# Controller_Board_DS-PI.net
KiCad netlist of a schematic drawn in EasyEDA Pro
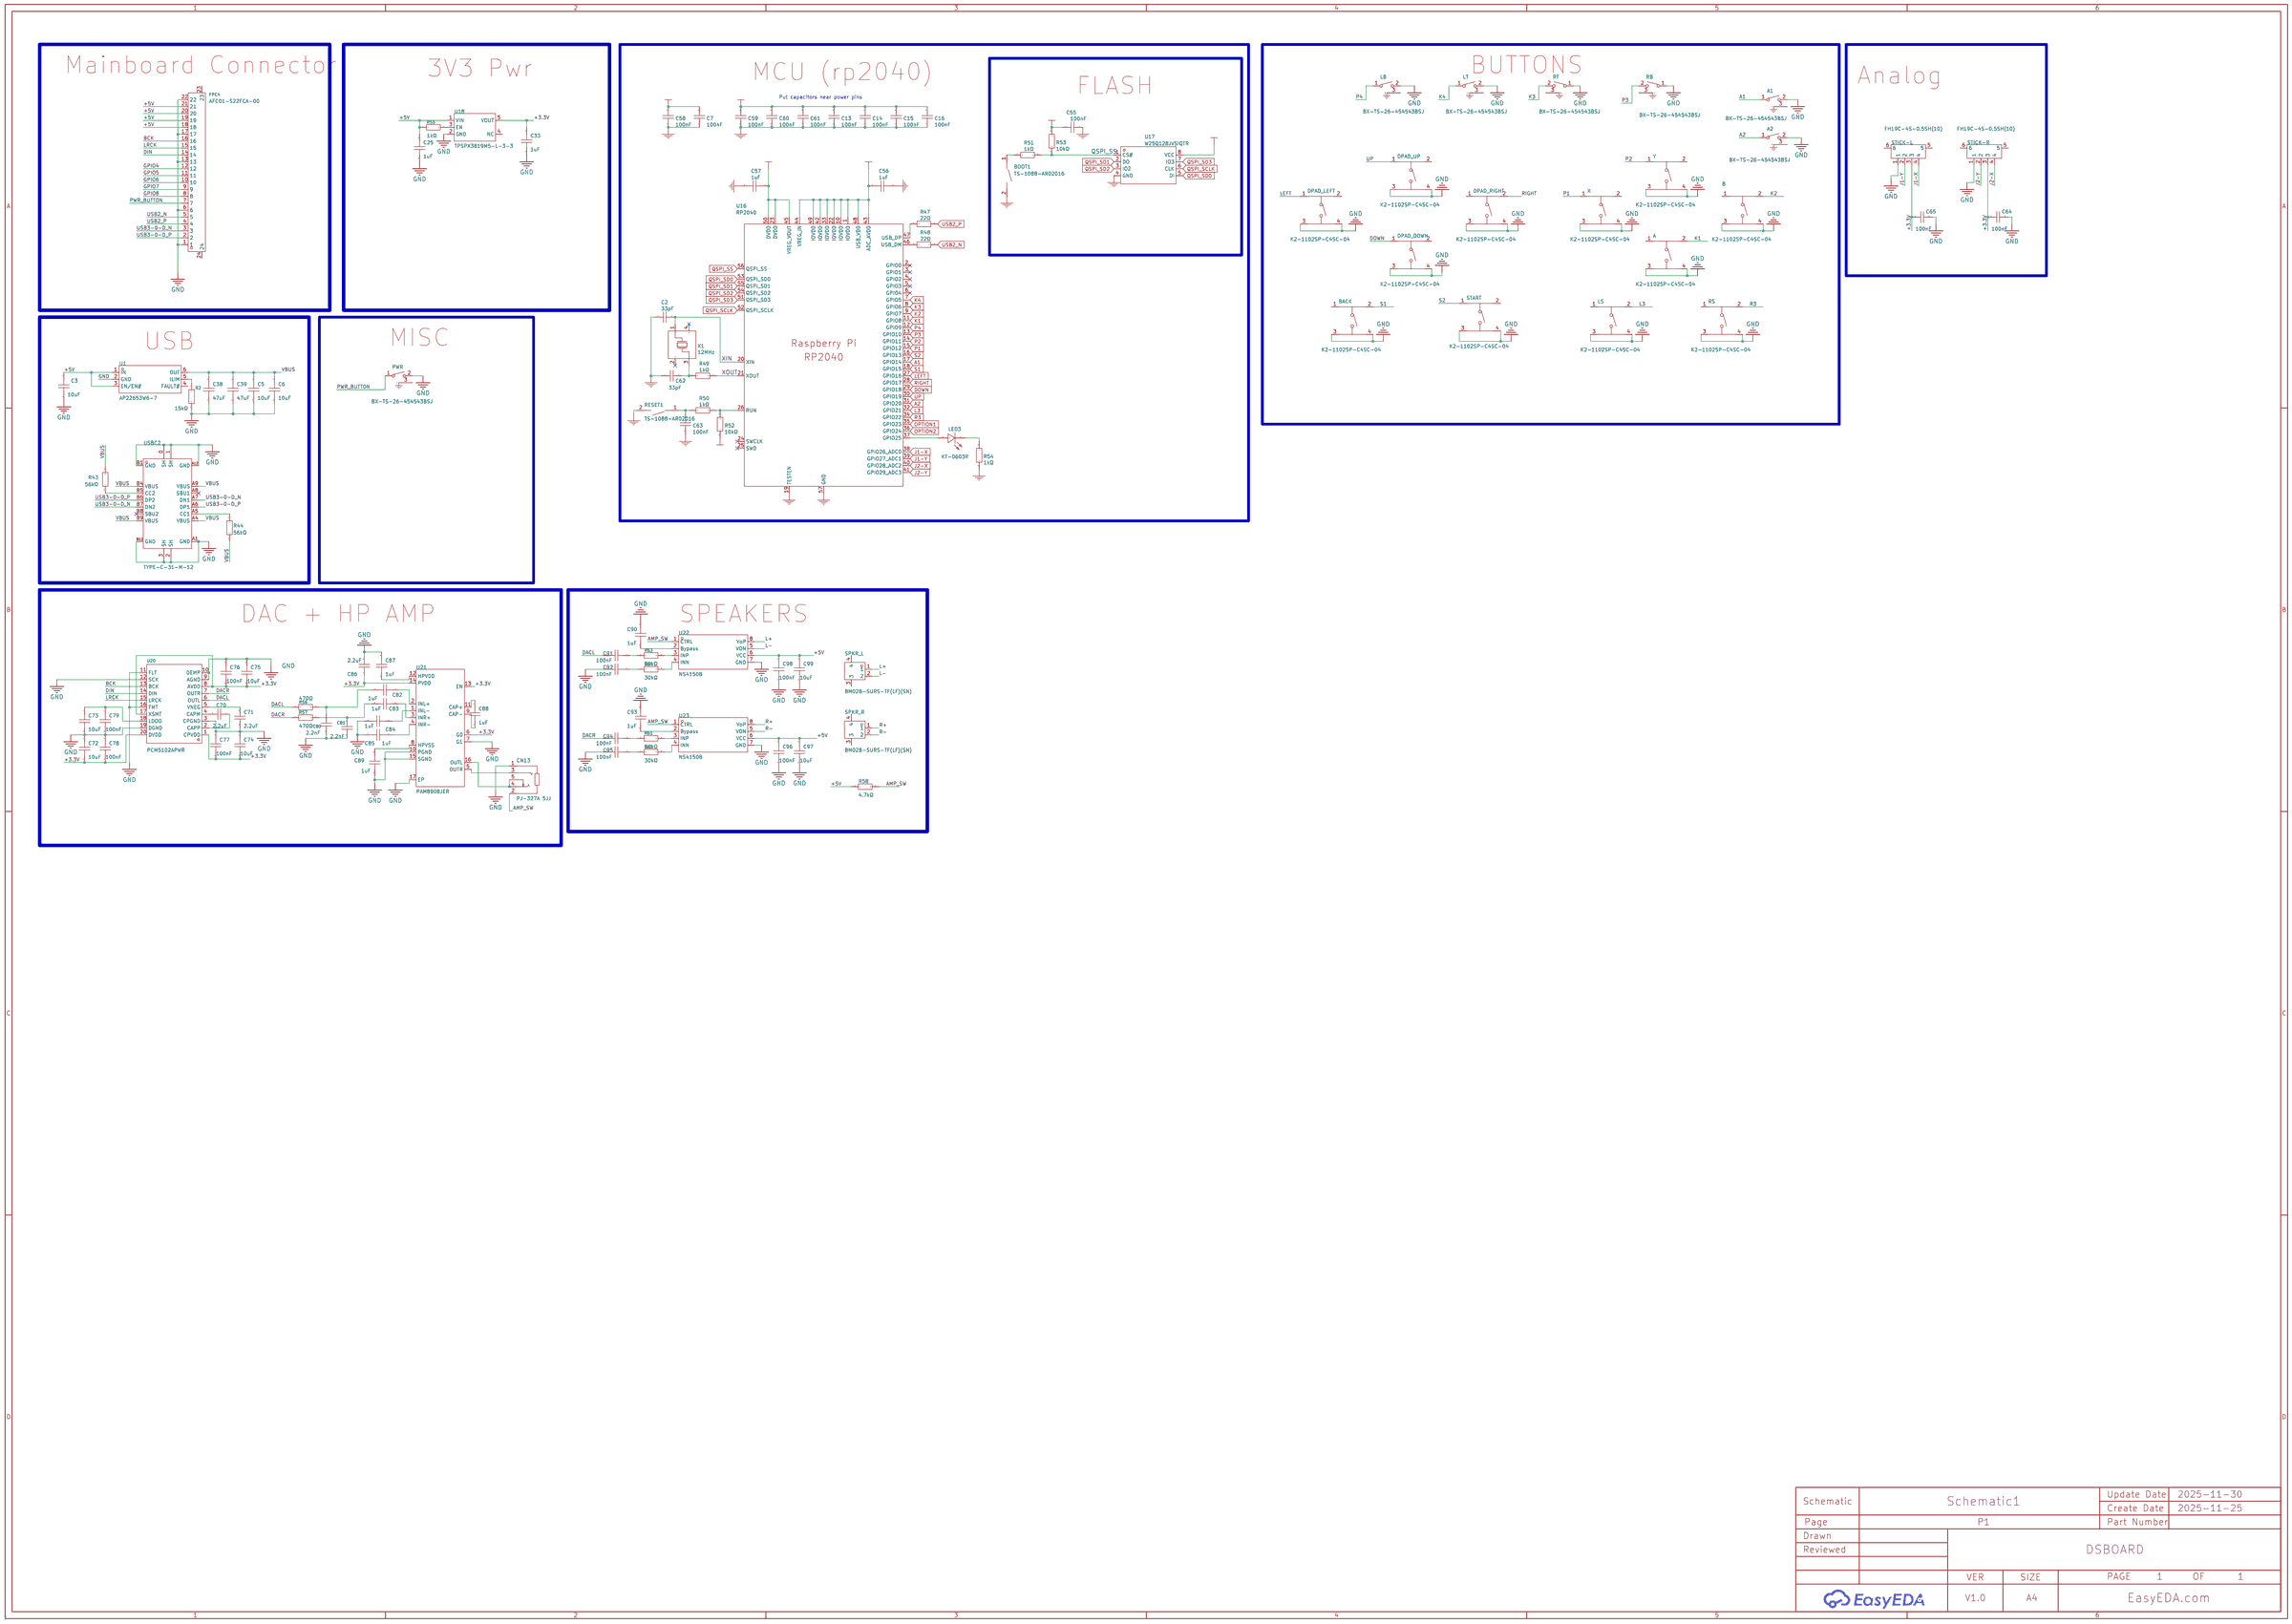
[diagram p0: schematic sheet]

(export (version "E")
  (design (tool "Eeschema 10.0.6"))
  (components
    (comp (ref "A")
      (value "K2-1102SP-C4SC-04")
      (footprint "easyedapro:KEY-SMD_4P-L6.0-W6.0-P4.50-LS9.5-BL")
      (fields (field (name "Manufacturer") "韩国韩荣"))
      (libsource (lib "easyedapro") (part "K2-1102SP-C4SC-04"))
    )
    (comp (ref "A1")
      (value "BX-TS-26-454543BSJ")
      (footprint "easyedapro:SW-TH_3P-L4.5-W4.3-P3.00-LS1.9")
      (fields (field (name "Manufacturer") "Bossie(博锡)"))
      (libsource (lib "easyedapro") (part "BX-TS-26-454543BSJ"))
    )
    (comp (ref "A2")
      (value "BX-TS-26-454543BSJ")
      (footprint "easyedapro:SW-TH_3P-L4.5-W4.3-P3.00-LS1.9")
      (fields (field (name "Manufacturer") "Bossie(博锡)"))
      (libsource (lib "easyedapro") (part "BX-TS-26-454543BSJ"))
    )
    (comp (ref "B")
      (value "K2-1102SP-C4SC-04")
      (footprint "easyedapro:KEY-SMD_4P-L6.0-W6.0-P4.50-LS9.5-BL")
      (fields (field (name "Manufacturer") "韩国韩荣"))
      (libsource (lib "easyedapro") (part "K2-1102SP-C4SC-04"))
    )
    (comp (ref "BACK")
      (value "K2-1102SP-C4SC-04")
      (footprint "easyedapro:KEY-SMD_4P-L6.0-W6.0-P4.50-LS9.5-BL")
      (fields (field (name "Manufacturer") "韩国韩荣"))
      (libsource (lib "easyedapro") (part "K2-1102SP-C4SC-04"))
    )
    (comp (ref "BOOT1")
      (value "TS-1088-AR02016")
      (footprint "easyedapro:SW-SMD_L3.9-W3.0-P4.45")
      (fields (field (name "Manufacturer") "XUNPU(讯普)"))
      (libsource (lib "easyedapro") (part "TS-1088-AR02016"))
    )
    (comp (ref "C2")
      (value "33pF")
      (footprint "easyedapro:C0402")
      (fields (field (name "Manufacturer Part") "0402CG330J500NT") (field (name "Manufacturer") "FH(风华)"))
      (libsource (lib "easyedapro") (part "33pF"))
    )
    (comp (ref "C3")
      (value "10uF")
      (footprint "easyedapro:C0805")
      (fields
        (field (name "Manufacturer Part") "CL21A106KAYNNNE")
        (field (name "Manufacturer") "SAMSUNG(三星)")
      )
      (libsource (lib "easyedapro") (part "CL21A106KAYNNNE"))
    )
    (comp (ref "C5")
      (value "10uF")
      (footprint "easyedapro:C0805")
      (fields
        (field (name "Manufacturer Part") "CL21A106KAYNNNE")
        (field (name "Manufacturer") "SAMSUNG(三星)")
      )
      (libsource (lib "easyedapro") (part "CL21A106KAYNNNE"))
    )
    (comp (ref "C6")
      (value "10uF")
      (footprint "easyedapro:C0805")
      (fields
        (field (name "Manufacturer Part") "CL21A106KAYNNNE")
        (field (name "Manufacturer") "SAMSUNG(三星)")
      )
      (libsource (lib "easyedapro") (part "CL21A106KAYNNNE"))
    )
    (comp (ref "C7")
      (value "100nF")
      (footprint "easyedapro:C0402_NEW")
      (fields
        (field (name "Manufacturer Part") "CL05B104KO5NNNC")
        (field (name "Manufacturer") "SAMSUNG(三星)")
      )
      (libsource (lib "easyedapro") (part "100nF"))
    )
    (comp (ref "C13")
      (value "100nF")
      (footprint "easyedapro:C0402_NEW")
      (fields
        (field (name "Manufacturer Part") "CL05B104KO5NNNC")
        (field (name "Manufacturer") "SAMSUNG(三星)")
      )
      (libsource (lib "easyedapro") (part "100nF"))
    )
    (comp (ref "C14")
      (value "100nF")
      (footprint "easyedapro:C0402_NEW")
      (fields
        (field (name "Manufacturer Part") "CL05B104KO5NNNC")
        (field (name "Manufacturer") "SAMSUNG(三星)")
      )
      (libsource (lib "easyedapro") (part "100nF"))
    )
    (comp (ref "C15")
      (value "100nF")
      (footprint "easyedapro:C0402_NEW")
      (fields
        (field (name "Manufacturer Part") "CL05B104KO5NNNC")
        (field (name "Manufacturer") "SAMSUNG(三星)")
      )
      (libsource (lib "easyedapro") (part "100nF"))
    )
    (comp (ref "C16")
      (value "100nF")
      (footprint "easyedapro:C0402_NEW")
      (fields
        (field (name "Manufacturer Part") "CL05B104KO5NNNC")
        (field (name "Manufacturer") "SAMSUNG(三星)")
      )
      (libsource (lib "easyedapro") (part "100nF"))
    )
    (comp (ref "C25")
      (value "1uF")
      (footprint "easyedapro:C0603")
      (fields
        (field (name "Manufacturer Part") "CL10A105KB8NNNC")
        (field (name "Manufacturer") "SAMSUNG(三星)")
      )
      (libsource (lib "easyedapro") (part "CL10A105KB8NNNC"))
    )
    (comp (ref "C33")
      (value "1uF")
      (footprint "easyedapro:C0603")
      (fields
        (field (name "Manufacturer Part") "CL10A105KB8NNNC")
        (field (name "Manufacturer") "SAMSUNG(三星)")
      )
      (libsource (lib "easyedapro") (part "CL10A105KB8NNNC"))
    )
    (comp (ref "C38")
      (value "47uF")
      (footprint "easyedapro:C1206")
      (fields
        (field (name "Manufacturer Part") "CL31A476MPHNNNE")
        (field (name "Manufacturer") "SAMSUNG(三星)")
      )
      (libsource (lib "easyedapro") (part "CL31A476MPHNNNE"))
    )
    (comp (ref "C39")
      (value "47uF")
      (footprint "easyedapro:C1206")
      (fields
        (field (name "Manufacturer Part") "CL31A476MPHNNNE")
        (field (name "Manufacturer") "SAMSUNG(三星)")
      )
      (libsource (lib "easyedapro") (part "CL31A476MPHNNNE"))
    )
    (comp (ref "C55")
      (value "100nF")
      (footprint "easyedapro:C0402_NEW")
      (fields
        (field (name "Manufacturer Part") "CL05B104KO5NNNC")
        (field (name "Manufacturer") "SAMSUNG(三星)")
      )
      (libsource (lib "easyedapro") (part "100nF"))
    )
    (comp (ref "C56")
      (value "1uF")
      (footprint "easyedapro:C0402")
      (fields
        (field (name "Manufacturer Part") "CL05A105KA5NQNC")
        (field (name "Manufacturer") "SAMSUNG(三星)")
      )
      (libsource (lib "easyedapro") (part "1uF"))
    )
    (comp (ref "C57")
      (value "1uF")
      (footprint "easyedapro:C0402")
      (fields
        (field (name "Manufacturer Part") "CL05A105KA5NQNC")
        (field (name "Manufacturer") "SAMSUNG(三星)")
      )
      (libsource (lib "easyedapro") (part "1uF"))
    )
    (comp (ref "C58")
      (value "100nF")
      (footprint "easyedapro:C0402_NEW")
      (fields
        (field (name "Manufacturer Part") "CL05B104KO5NNNC")
        (field (name "Manufacturer") "SAMSUNG(三星)")
      )
      (libsource (lib "easyedapro") (part "100nF"))
    )
    (comp (ref "C59")
      (value "100nF")
      (footprint "easyedapro:C0402_NEW")
      (fields
        (field (name "Manufacturer Part") "CL05B104KO5NNNC")
        (field (name "Manufacturer") "SAMSUNG(三星)")
      )
      (libsource (lib "easyedapro") (part "100nF"))
    )
    (comp (ref "C60")
      (value "100nF")
      (footprint "easyedapro:C0402_NEW")
      (fields
        (field (name "Manufacturer Part") "CL05B104KO5NNNC")
        (field (name "Manufacturer") "SAMSUNG(三星)")
      )
      (libsource (lib "easyedapro") (part "100nF"))
    )
    (comp (ref "C61")
      (value "100nF")
      (footprint "easyedapro:C0402_NEW")
      (fields
        (field (name "Manufacturer Part") "CL05B104KO5NNNC")
        (field (name "Manufacturer") "SAMSUNG(三星)")
      )
      (libsource (lib "easyedapro") (part "100nF"))
    )
    (comp (ref "C62")
      (value "33pF")
      (footprint "easyedapro:C0402")
      (fields (field (name "Manufacturer Part") "0402CG330J500NT") (field (name "Manufacturer") "FH(风华)"))
      (libsource (lib "easyedapro") (part "33pF"))
    )
    (comp (ref "C63")
      (value "100nF")
      (footprint "easyedapro:C0402_NEW")
      (fields
        (field (name "Manufacturer Part") "CL05B104KO5NNNC")
        (field (name "Manufacturer") "SAMSUNG(三星)")
      )
      (libsource (lib "easyedapro") (part "100nF"))
    )
    (comp (ref "C64")
      (value "100nF")
      (footprint "easyedapro:C0402_NEW")
      (fields
        (field (name "Manufacturer Part") "CL05B104KO5NNNC")
        (field (name "Manufacturer") "SAMSUNG(三星)")
      )
      (libsource (lib "easyedapro") (part "100nF"))
    )
    (comp (ref "C65")
      (value "100nF")
      (footprint "easyedapro:C0402_NEW")
      (fields
        (field (name "Manufacturer Part") "CL05B104KO5NNNC")
        (field (name "Manufacturer") "SAMSUNG(三星)")
      )
      (libsource (lib "easyedapro") (part "100nF"))
    )
    (comp (ref "C70")
      (value "2.2uF")
      (footprint "easyedapro:C0603")
      (fields
        (field (name "Manufacturer Part") "CL10A225KO8NNNC")
        (field (name "Manufacturer") "SAMSUNG(三星)")
      )
      (libsource (lib "easyedapro") (part "CL10A225KO8NNNC"))
    )
    (comp (ref "C71")
      (value "2.2uF")
      (footprint "easyedapro:C0603")
      (fields
        (field (name "Manufacturer Part") "CL10A225KO8NNNC")
        (field (name "Manufacturer") "SAMSUNG(三星)")
      )
      (libsource (lib "easyedapro") (part "CL10A225KO8NNNC"))
    )
    (comp (ref "C72")
      (value "10uF")
      (footprint "easyedapro:C0805")
      (fields
        (field (name "Manufacturer Part") "GRM21BR61H106KE43L")
        (field (name "Manufacturer") "muRata(村田)")
      )
      (libsource (lib "easyedapro") (part "GRM21BR61H106KE43L"))
    )
    (comp (ref "C73")
      (value "10uF")
      (footprint "easyedapro:C0805")
      (fields
        (field (name "Manufacturer Part") "GRM21BR61H106KE43L")
        (field (name "Manufacturer") "muRata(村田)")
      )
      (libsource (lib "easyedapro") (part "GRM21BR61H106KE43L"))
    )
    (comp (ref "C74")
      (value "10uF")
      (footprint "easyedapro:C0805")
      (fields
        (field (name "Manufacturer Part") "GRM21BR61H106KE43L")
        (field (name "Manufacturer") "muRata(村田)")
      )
      (libsource (lib "easyedapro") (part "GRM21BR61H106KE43L"))
    )
    (comp (ref "C75")
      (value "10uF")
      (footprint "easyedapro:C0805")
      (fields
        (field (name "Manufacturer Part") "GRM21BR61H106KE43L")
        (field (name "Manufacturer") "muRata(村田)")
      )
      (libsource (lib "easyedapro") (part "GRM21BR61H106KE43L"))
    )
    (comp (ref "C76")
      (value "100nF")
      (footprint "easyedapro:C0603")
      (description "Capacitance:100nF Tolerance:±10% Tolerance:±10% Voltage Rating:50V Temperature Coefficient:X7R")
      (fields
        (field (name "Manufacturer Part") "CC0603KRX7R9BB104")
        (field (name "Manufacturer") "YAGEO(国巨)")
      )
      (libsource (lib "easyedapro") (part "CC0603KRX7R9BB104"))
    )
    (comp (ref "C77")
      (value "100nF")
      (footprint "easyedapro:C0603")
      (description "Capacitance:100nF Tolerance:±10% Tolerance:±10% Voltage Rating:50V Temperature Coefficient:X7R")
      (fields
        (field (name "Manufacturer Part") "CC0603KRX7R9BB104")
        (field (name "Manufacturer") "YAGEO(国巨)")
      )
      (libsource (lib "easyedapro") (part "CC0603KRX7R9BB104"))
    )
    (comp (ref "C78")
      (value "100nF")
      (footprint "easyedapro:C0603")
      (description "Capacitance:100nF Tolerance:±10% Tolerance:±10% Voltage Rating:50V Temperature Coefficient:X7R")
      (fields
        (field (name "Manufacturer Part") "CC0603KRX7R9BB104")
        (field (name "Manufacturer") "YAGEO(国巨)")
      )
      (libsource (lib "easyedapro") (part "CC0603KRX7R9BB104"))
    )
    (comp (ref "C79")
      (value "100nF")
      (footprint "easyedapro:C0603")
      (description "Capacitance:100nF Tolerance:±10% Tolerance:±10% Voltage Rating:50V Temperature Coefficient:X7R")
      (fields
        (field (name "Manufacturer Part") "CC0603KRX7R9BB104")
        (field (name "Manufacturer") "YAGEO(国巨)")
      )
      (libsource (lib "easyedapro") (part "CC0603KRX7R9BB104"))
    )
    (comp (ref "C80")
      (value "2.2nF")
      (footprint "easyedapro:C0805")
      (fields
        (field (name "Manufacturer Part") "CL21C222JBFNNNE")
        (field (name "Manufacturer") "SAMSUNG(三星)")
      )
      (libsource (lib "easyedapro") (part "CL21C222JBFNNNE"))
    )
    (comp (ref "C81")
      (value "2.2nF")
      (footprint "easyedapro:C0805")
      (fields
        (field (name "Manufacturer Part") "CL21C222JBFNNNE")
        (field (name "Manufacturer") "SAMSUNG(三星)")
      )
      (libsource (lib "easyedapro") (part "CL21C222JBFNNNE"))
    )
    (comp (ref "C82")
      (value "1uF")
      (footprint "easyedapro:C0603")
      (fields
        (field (name "Manufacturer Part") "CL10A105KB8NNNC")
        (field (name "Manufacturer") "SAMSUNG(三星)")
      )
      (libsource (lib "easyedapro") (part "CL10A105KB8NNNC"))
    )
    (comp (ref "C83")
      (value "1uF")
      (footprint "easyedapro:C0603")
      (fields
        (field (name "Manufacturer Part") "CL10A105KB8NNNC")
        (field (name "Manufacturer") "SAMSUNG(三星)")
      )
      (libsource (lib "easyedapro") (part "CL10A105KB8NNNC"))
    )
    (comp (ref "C84")
      (value "1uF")
      (footprint "easyedapro:C0603")
      (fields
        (field (name "Manufacturer Part") "CL10A105KB8NNNC")
        (field (name "Manufacturer") "SAMSUNG(三星)")
      )
      (libsource (lib "easyedapro") (part "CL10A105KB8NNNC"))
    )
    (comp (ref "C85")
      (value "1uF")
      (footprint "easyedapro:C0603")
      (fields
        (field (name "Manufacturer Part") "CL10A105KB8NNNC")
        (field (name "Manufacturer") "SAMSUNG(三星)")
      )
      (libsource (lib "easyedapro") (part "CL10A105KB8NNNC"))
    )
    (comp (ref "C86")
      (value "2.2uF")
      (footprint "easyedapro:C0603")
      (fields
        (field (name "Manufacturer Part") "CL10A225KO8NNNC")
        (field (name "Manufacturer") "SAMSUNG(三星)")
      )
      (libsource (lib "easyedapro") (part "CL10A225KO8NNNC"))
    )
    (comp (ref "C87")
      (value "1uF")
      (footprint "easyedapro:C0603")
      (fields
        (field (name "Manufacturer Part") "CL10A105KB8NNNC")
        (field (name "Manufacturer") "SAMSUNG(三星)")
      )
      (libsource (lib "easyedapro") (part "CL10A105KB8NNNC"))
    )
    (comp (ref "C88")
      (value "1uF")
      (footprint "easyedapro:C0603")
      (fields
        (field (name "Manufacturer Part") "CL10A105KB8NNNC")
        (field (name "Manufacturer") "SAMSUNG(三星)")
      )
      (libsource (lib "easyedapro") (part "CL10A105KB8NNNC"))
    )
    (comp (ref "C89")
      (value "1uF")
      (footprint "easyedapro:C0603")
      (fields
        (field (name "Manufacturer Part") "CL10A105KB8NNNC")
        (field (name "Manufacturer") "SAMSUNG(三星)")
      )
      (libsource (lib "easyedapro") (part "CL10A105KB8NNNC"))
    )
    (comp (ref "C90")
      (value "1uF")
      (footprint "easyedapro:C0603")
      (fields
        (field (name "Manufacturer Part") "CL10A105KB8NNNC")
        (field (name "Manufacturer") "SAMSUNG(三星)")
      )
      (libsource (lib "easyedapro") (part "CL10A105KB8NNNC"))
    )
    (comp (ref "C91")
      (value "100nF")
      (footprint "easyedapro:C0402")
      (fields
        (field (name "Manufacturer Part") "CL05B104KB54PNC")
        (field (name "Manufacturer") "SAMSUNG(三星)")
      )
      (libsource (lib "easyedapro") (part "CL05B104KB54PNC"))
    )
    (comp (ref "C92")
      (value "100nF")
      (footprint "easyedapro:C0402")
      (fields
        (field (name "Manufacturer Part") "CL05B104KB54PNC")
        (field (name "Manufacturer") "SAMSUNG(三星)")
      )
      (libsource (lib "easyedapro") (part "CL05B104KB54PNC"))
    )
    (comp (ref "C93")
      (value "1uF")
      (footprint "easyedapro:C0603")
      (fields
        (field (name "Manufacturer Part") "CL10A105KB8NNNC")
        (field (name "Manufacturer") "SAMSUNG(三星)")
      )
      (libsource (lib "easyedapro") (part "CL10A105KB8NNNC"))
    )
    (comp (ref "C94")
      (value "100nF")
      (footprint "easyedapro:C0402")
      (fields
        (field (name "Manufacturer Part") "CL05B104KB54PNC")
        (field (name "Manufacturer") "SAMSUNG(三星)")
      )
      (libsource (lib "easyedapro") (part "CL05B104KB54PNC"))
    )
    (comp (ref "C95")
      (value "100nF")
      (footprint "easyedapro:C0402")
      (fields
        (field (name "Manufacturer Part") "CL05B104KB54PNC")
        (field (name "Manufacturer") "SAMSUNG(三星)")
      )
      (libsource (lib "easyedapro") (part "CL05B104KB54PNC"))
    )
    (comp (ref "C96")
      (value "100nF")
      (footprint "easyedapro:C0402")
      (fields
        (field (name "Manufacturer Part") "CL05B104KB54PNC")
        (field (name "Manufacturer") "SAMSUNG(三星)")
      )
      (libsource (lib "easyedapro") (part "CL05B104KB54PNC"))
    )
    (comp (ref "C97")
      (value "10uF")
      (footprint "easyedapro:C0805")
      (fields
        (field (name "Manufacturer Part") "CL21A106KAYNNNE")
        (field (name "Manufacturer") "SAMSUNG(三星)")
      )
      (libsource (lib "easyedapro") (part "CL21A106KAYNNNE"))
    )
    (comp (ref "C98")
      (value "100nF")
      (footprint "easyedapro:C0402")
      (fields
        (field (name "Manufacturer Part") "CL05B104KB54PNC")
        (field (name "Manufacturer") "SAMSUNG(三星)")
      )
      (libsource (lib "easyedapro") (part "CL05B104KB54PNC"))
    )
    (comp (ref "C99")
      (value "10uF")
      (footprint "easyedapro:C0805")
      (fields
        (field (name "Manufacturer Part") "CL21A106KAYNNNE")
        (field (name "Manufacturer") "SAMSUNG(三星)")
      )
      (libsource (lib "easyedapro") (part "CL21A106KAYNNNE"))
    )
    (comp (ref "CN13")
      (value "PJ-327A 5JJ")
      (footprint "easyedapro:AUDIO-SMD_PJ-327A5JJ")
      (fields (field (name "Manufacturer") "SHOU HAN(首韩)"))
      (libsource (lib "easyedapro") (part "PJ-327A 5JJ"))
    )
    (comp (ref "DPAD_DOWN")
      (value "K2-1102SP-C4SC-04")
      (footprint "easyedapro:KEY-SMD_4P-L6.0-W6.0-P4.50-LS9.5-BL")
      (fields (field (name "Manufacturer") "韩国韩荣"))
      (libsource (lib "easyedapro") (part "K2-1102SP-C4SC-04"))
    )
    (comp (ref "DPAD_LEFT")
      (value "K2-1102SP-C4SC-04")
      (footprint "easyedapro:KEY-SMD_4P-L6.0-W6.0-P4.50-LS9.5-BL")
      (fields (field (name "Manufacturer") "韩国韩荣"))
      (libsource (lib "easyedapro") (part "K2-1102SP-C4SC-04"))
    )
    (comp (ref "DPAD_RIGHT")
      (value "K2-1102SP-C4SC-04")
      (footprint "easyedapro:KEY-SMD_4P-L6.0-W6.0-P4.50-LS9.5-BL")
      (fields (field (name "Manufacturer") "韩国韩荣"))
      (libsource (lib "easyedapro") (part "K2-1102SP-C4SC-04"))
    )
    (comp (ref "DPAD_UP")
      (value "K2-1102SP-C4SC-04")
      (footprint "easyedapro:KEY-SMD_4P-L6.0-W6.0-P4.50-LS9.5-BL")
      (fields (field (name "Manufacturer") "韩国韩荣"))
      (libsource (lib "easyedapro") (part "K2-1102SP-C4SC-04"))
    )
    (comp (ref "FPC4")
      (value "AFC01-S22FCA-00")
      (fields (field (name "Manufacturer") "JS(钜硕电子)"))
      (libsource (lib "easyedapro") (part "fh12-22s-0.5sh(55)"))
    )
    (comp (ref "LB")
      (value "BX-TS-26-454543BSJ")
      (footprint "easyedapro:SW-TH_3P-L4.5-W4.3-P3.00-LS1.9")
      (fields (field (name "Manufacturer") "Bossie(博锡)"))
      (libsource (lib "easyedapro") (part "BX-TS-26-454543BSJ"))
    )
    (comp (ref "LED3")
      (value "KT-0603R")
      (footprint "easyedapro:LED0603-RD")
      (fields (field (name "Manufacturer") "KENTO"))
      (libsource (lib "easyedapro") (part "KT-0603R"))
    )
    (comp (ref "LS")
      (value "K2-1102SP-C4SC-04")
      (footprint "easyedapro:KEY-SMD_4P-L6.0-W6.0-P4.50-LS9.5-BL")
      (fields (field (name "Manufacturer") "韩国韩荣"))
      (libsource (lib "easyedapro") (part "K2-1102SP-C4SC-04"))
    )
    (comp (ref "LT")
      (value "BX-TS-26-454543BSJ")
      (footprint "easyedapro:SW-TH_3P-L4.5-W4.3-P3.00-LS1.9")
      (fields (field (name "Manufacturer") "Bossie(博锡)"))
      (libsource (lib "easyedapro") (part "BX-TS-26-454543BSJ"))
    )
    (comp (ref "PWR")
      (value "BX-TS-26-454543BSJ")
      (footprint "easyedapro:SW-TH_3P-L4.5-W4.3-P3.00-LS1.9")
      (fields (field (name "Manufacturer") "Bossie(博锡)"))
      (libsource (lib "easyedapro") (part "BX-TS-26-454543BSJ"))
    )
    (comp (ref "R2")
      (value "15kΩ")
      (footprint "easyedapro:R0402")
      (fields
        (field (name "Manufacturer Part") "0402WGF1502TCE")
        (field (name "Manufacturer") "UNI-ROYAL(厚声)")
      )
      (libsource (lib "easyedapro") (part "0402WGF1502TCE"))
    )
    (comp (ref "R43")
      (value "56kΩ")
      (footprint "easyedapro:R0402")
      (fields
        (field (name "Manufacturer Part") "0402WGF5602TCE")
        (field (name "Manufacturer") "UNI-ROYAL(厚声)")
      )
      (libsource (lib "easyedapro") (part "0402WGF5602TCE"))
    )
    (comp (ref "R44")
      (value "56kΩ")
      (footprint "easyedapro:R0402")
      (fields
        (field (name "Manufacturer Part") "0402WGF5602TCE")
        (field (name "Manufacturer") "UNI-ROYAL(厚声)")
      )
      (libsource (lib "easyedapro") (part "0402WGF5602TCE"))
    )
    (comp (ref "R47")
      (value "22Ω")
      (footprint "easyedapro:R0402")
      (fields
        (field (name "Manufacturer Part") "0402WGF220JTCE")
        (field (name "Manufacturer") "UNI-ROYAL(厚声)")
      )
      (libsource (lib "easyedapro") (part "22Ω"))
    )
    (comp (ref "R48")
      (value "22Ω")
      (footprint "easyedapro:R0402")
      (fields
        (field (name "Manufacturer Part") "0402WGF220JTCE")
        (field (name "Manufacturer") "UNI-ROYAL(厚声)")
      )
      (libsource (lib "easyedapro") (part "22Ω"))
    )
    (comp (ref "R49")
      (value "1kΩ")
      (footprint "easyedapro:R0402")
      (fields
        (field (name "Manufacturer Part") "0402WGF1001TCE")
        (field (name "Manufacturer") "UNI-ROYAL(厚声)")
      )
      (libsource (lib "easyedapro") (part "1kΩ"))
    )
    (comp (ref "R50")
      (value "1kΩ")
      (footprint "easyedapro:R0402")
      (fields
        (field (name "Manufacturer Part") "0402WGF1001TCE")
        (field (name "Manufacturer") "UNI-ROYAL(厚声)")
      )
      (libsource (lib "easyedapro") (part "1kΩ"))
    )
    (comp (ref "R51")
      (value "1kΩ")
      (footprint "easyedapro:R0402")
      (fields
        (field (name "Manufacturer Part") "0402WGF1001TCE")
        (field (name "Manufacturer") "UNI-ROYAL(厚声)")
      )
      (libsource (lib "easyedapro") (part "1kΩ"))
    )
    (comp (ref "R52")
      (value "10kΩ")
      (footprint "easyedapro:R0402")
      (fields
        (field (name "Manufacturer Part") "0402WGF1002TCE")
        (field (name "Manufacturer") "UNI-ROYAL(厚声)")
      )
      (libsource (lib "easyedapro") (part "10kΩ"))
    )
    (comp (ref "R53")
      (value "10kΩ")
      (footprint "easyedapro:R0402")
      (fields
        (field (name "Manufacturer Part") "0402WGF1002TCE")
        (field (name "Manufacturer") "UNI-ROYAL(厚声)")
      )
      (libsource (lib "easyedapro") (part "10kΩ"))
    )
    (comp (ref "R54")
      (value "1kΩ")
      (footprint "easyedapro:R0402")
      (fields
        (field (name "Manufacturer Part") "0402WGF1001TCE")
        (field (name "Manufacturer") "UNI-ROYAL(厚声)")
      )
      (libsource (lib "easyedapro") (part "1kΩ"))
    )
    (comp (ref "R55")
      (value "1kΩ")
      (footprint "easyedapro:R0402")
      (fields
        (field (name "Manufacturer Part") "0402WGF1001TCE")
        (field (name "Manufacturer") "UNI-ROYAL(厚声)")
      )
      (libsource (lib "easyedapro") (part "0402WGF1001TCE"))
    )
    (comp (ref "R56")
      (value "470Ω")
      (footprint "easyedapro:R0805")
      (fields
        (field (name "Manufacturer Part") "0805W8F4700T5E")
        (field (name "Manufacturer") "UNI-ROYAL(厚声)")
      )
      (libsource (lib "easyedapro") (part "0805W8F4700T5E"))
    )
    (comp (ref "R57")
      (value "470Ω")
      (footprint "easyedapro:R0805")
      (fields
        (field (name "Manufacturer Part") "0805W8F4700T5E")
        (field (name "Manufacturer") "UNI-ROYAL(厚声)")
      )
      (libsource (lib "easyedapro") (part "0805W8F4700T5E"))
    )
    (comp (ref "R58")
      (value "4.7kΩ")
      (footprint "easyedapro:R0603")
      (fields
        (field (name "Manufacturer Part") "0603WAF4701T5E")
        (field (name "Manufacturer") "UNI-ROYAL(厚声)")
      )
      (libsource (lib "easyedapro") (part "0603WAF4701T5E"))
    )
    (comp (ref "R61")
      (value "30kΩ")
      (footprint "easyedapro:R0603")
      (fields
        (field (name "Manufacturer Part") "0603WAF3002T5E")
        (field (name "Manufacturer") "UNI-ROYAL(厚声)")
      )
      (libsource (lib "easyedapro") (part "0603WAF3002T5E"))
    )
    (comp (ref "R62")
      (value "30kΩ")
      (footprint "easyedapro:R0603")
      (fields
        (field (name "Manufacturer Part") "0603WAF3002T5E")
        (field (name "Manufacturer") "UNI-ROYAL(厚声)")
      )
      (libsource (lib "easyedapro") (part "0603WAF3002T5E"))
    )
    (comp (ref "R63")
      (value "30kΩ")
      (footprint "easyedapro:R0603")
      (fields
        (field (name "Manufacturer Part") "0603WAF3002T5E")
        (field (name "Manufacturer") "UNI-ROYAL(厚声)")
      )
      (libsource (lib "easyedapro") (part "0603WAF3002T5E"))
    )
    (comp (ref "R64")
      (value "30kΩ")
      (footprint "easyedapro:R0603")
      (fields
        (field (name "Manufacturer Part") "0603WAF3002T5E")
        (field (name "Manufacturer") "UNI-ROYAL(厚声)")
      )
      (libsource (lib "easyedapro") (part "0603WAF3002T5E"))
    )
    (comp (ref "RB")
      (value "BX-TS-26-454543BSJ")
      (footprint "easyedapro:SW-TH_3P-L4.5-W4.3-P3.00-LS1.9")
      (fields (field (name "Manufacturer") "Bossie(博锡)"))
      (libsource (lib "easyedapro") (part "BX-TS-26-454543BSJ"))
    )
    (comp (ref "RESET1")
      (value "TS-1088-AR02016")
      (footprint "easyedapro:SW-SMD_L3.9-W3.0-P4.45")
      (fields (field (name "Manufacturer") "XUNPU(讯普)"))
      (libsource (lib "easyedapro") (part "TS-1088-AR02016"))
    )
    (comp (ref "RS")
      (value "K2-1102SP-C4SC-04")
      (footprint "easyedapro:KEY-SMD_4P-L6.0-W6.0-P4.50-LS9.5-BL")
      (fields (field (name "Manufacturer") "韩国韩荣"))
      (libsource (lib "easyedapro") (part "K2-1102SP-C4SC-04"))
    )
    (comp (ref "RT")
      (value "BX-TS-26-454543BSJ")
      (footprint "easyedapro:SW-TH_3P-L4.5-W4.3-P3.00-LS1.9")
      (fields (field (name "Manufacturer") "Bossie(博锡)"))
      (libsource (lib "easyedapro") (part "BX-TS-26-454543BSJ"))
    )
    (comp (ref "SPKR_L")
      (value "BM02B-SURS-TF(LF)(SN)")
      (footprint "easyedapro:CONN-SMD_2P-P0.80_BM02B-SURS-TF-LF-SN")
      (fields (field (name "Manufacturer") "JST"))
      (libsource (lib "easyedapro") (part "BM02B-SURS-TF(LF)(SN)"))
    )
    (comp (ref "SPKR_R")
      (value "BM02B-SURS-TF(LF)(SN)")
      (footprint "easyedapro:CONN-SMD_2P-P0.80_BM02B-SURS-TF-LF-SN")
      (fields (field (name "Manufacturer") "JST"))
      (libsource (lib "easyedapro") (part "BM02B-SURS-TF(LF)(SN)"))
    )
    (comp (ref "START")
      (value "K2-1102SP-C4SC-04")
      (footprint "easyedapro:KEY-SMD_4P-L6.0-W6.0-P4.50-LS9.5-BL")
      (fields (field (name "Manufacturer") "韩国韩荣"))
      (libsource (lib "easyedapro") (part "K2-1102SP-C4SC-04"))
    )
    (comp (ref "STICK-L")
      (value "FH19C-4S-0.5SH(10)")
      (fields (field (name "Manufacturer") "HRS(广濑)"))
      (libsource (lib "easyedapro") (part "fh34srj-4s-0.5sh(50)"))
    )
    (comp (ref "STICK-R")
      (value "FH19C-4S-0.5SH(10)")
      (fields (field (name "Manufacturer") "HRS(广濑)"))
      (libsource (lib "easyedapro") (part "fh34srj-4s-0.5sh(50)"))
    )
    (comp (ref "U1")
      (value "AP22653W6-7")
      (footprint "easyedapro:SOT-23-6_L2.9-W1.6-P0.95-LS2.8-BR")
      (fields (field (name "Manufacturer") "DIODES(美台)"))
      (libsource (lib "easyedapro") (part "AP22653W6-7"))
    )
    (comp (ref "U16")
      (value "RP2040")
      (footprint "easyedapro:LQFN-56_L7.0-W7.0-P0.4-EP")
      (fields (field (name "Manufacturer") "Raspberry Pi(树莓派)"))
      (libsource (lib "easyedapro") (part "RP2040"))
    )
    (comp (ref "U17")
      (value "W25Q128JVSIQTR")
      (footprint "easyedapro:SOIC-8_L5.3-W5.3-P1.27-LS8.0-BL")
      (fields (field (name "Manufacturer Part") "W25Q128JVSIQ") (field (name "Manufacturer") "WINBOND(华邦)"))
      (libsource (lib "easyedapro") (part "W25Q128JVSIQTR"))
    )
    (comp (ref "U18")
      (value "TPSPX3819M5-L-3-3")
      (footprint "easyedapro:SOT-23-5_L3.0-W1.6-P0.95-LS2.8-BR")
      (fields (field (name "Manufacturer") "TECH PUBLIC(台舟)"))
      (libsource (lib "easyedapro") (part "TPSPX3819M5-L-3-3"))
    )
    (comp (ref "U20")
      (value "PCM5102APWR")
      (footprint "easyedapro:TSSOP-20_L6.5-W4.4-P0.65-LS6.4-BL")
      (fields (field (name "Manufacturer") "TI(德州仪器)"))
      (libsource (lib "easyedapro") (part "PCM5102APWR"))
    )
    (comp (ref "U21")
      (value "PAM8908JER")
      (footprint "easyedapro:QFN-16_L3.0-W3.0-P0.50-BL-EP1.7")
      (fields (field (name "Manufacturer") "DIODES(美台)"))
      (libsource (lib "easyedapro") (part "PAM8908JER"))
    )
    (comp (ref "U22")
      (value "NS4150B")
      (footprint "easyedapro:MSOP-8_L3.0-W3.0-P0.65-LS5.0-BL")
      (description "Class:Class D Output Power:3Wx1@4Ω Voltage - Supply:3V~5.25V Voltage - Supply:3V~5.25V")
      (fields (field (name "Manufacturer") "Nsiway(纳芯威)"))
      (libsource (lib "easyedapro") (part "NS4150"))
    )
    (comp (ref "U23")
      (value "NS4150B")
      (footprint "easyedapro:MSOP-8_L3.0-W3.0-P0.65-LS5.0-BL")
      (description "Class:Class D Output Power:3Wx1@4Ω Voltage - Supply:3V~5.25V Voltage - Supply:3V~5.25V")
      (fields (field (name "Manufacturer") "Nsiway(纳芯威)"))
      (libsource (lib "easyedapro") (part "NS4150"))
    )
    (comp (ref "USBC2")
      (value "TYPE-C-31-M-12")
      (footprint "easyedapro:USB-C_SMD-TYPE-C-31-M-12")
      (fields (field (name "Manufacturer") "韩国韩荣"))
      (libsource (lib "easyedapro") (part "TYPE-C-31-M-12"))
    )
    (comp (ref "X")
      (value "K2-1102SP-C4SC-04")
      (footprint "easyedapro:KEY-SMD_4P-L6.0-W6.0-P4.50-LS9.5-BL")
      (fields (field (name "Manufacturer") "韩国韩荣"))
      (libsource (lib "easyedapro") (part "K2-1102SP-C4SC-04"))
    )
    (comp (ref "X1")
      (value "12MHz")
      (footprint "easyedapro:OSC-SMD_4P-L3.2-W2.5-BL")
      (fields (field (name "Manufacturer Part") "X322512MSB4SI") (field (name "Manufacturer") "YXC"))
      (libsource (lib "easyedapro") (part "12MHz"))
    )
    (comp (ref "Y")
      (value "K2-1102SP-C4SC-04")
      (footprint "easyedapro:KEY-SMD_4P-L6.0-W6.0-P4.50-LS9.5-BL")
      (fields (field (name "Manufacturer") "韩国韩荣"))
      (libsource (lib "easyedapro") (part "K2-1102SP-C4SC-04"))
    )
  )
  (nets
    (net (code "1") (name "+1V1") (class "Default")
      (node (ref "C57") (pin "1") (pinfunction "1_1") (pintype "unspecified"))
      (node (ref "C58") (pin "2") (pinfunction "2_2") (pintype "input"))
      (node (ref "C7") (pin "2") (pinfunction "2_2") (pintype "input"))
      (node (ref "U16") (pin "23") (pinfunction "DVDD_23") (pintype "bidirectional"))
      (node (ref "U16") (pin "45") (pinfunction "VREG_VOUT_45") (pintype "bidirectional"))
      (node (ref "U16") (pin "50") (pinfunction "DVDD_50") (pintype "bidirectional"))
    )
    (net (code "2") (name "+3.3V") (class "Default")
      (node (ref "C13") (pin "2") (pinfunction "2_2") (pintype "input"))
      (node (ref "C14") (pin "2") (pinfunction "2_2") (pintype "input"))
      (node (ref "C15") (pin "2") (pinfunction "2_2") (pintype "input"))
      (node (ref "C16") (pin "2") (pinfunction "2_2") (pintype "input"))
      (node (ref "C33") (pin "1") (pinfunction "1_1") (pintype "unspecified"))
      (node (ref "C55") (pin "2") (pinfunction "2_2") (pintype "input"))
      (node (ref "C56") (pin "1") (pinfunction "1_1") (pintype "unspecified"))
      (node (ref "C59") (pin "2") (pinfunction "2_2") (pintype "input"))
      (node (ref "C60") (pin "2") (pinfunction "2_2") (pintype "input"))
      (node (ref "C61") (pin "2") (pinfunction "2_2") (pintype "input"))
      (node (ref "C64") (pin "1") (pinfunction "1_1") (pintype "input"))
      (node (ref "C65") (pin "1") (pinfunction "1_1") (pintype "input"))
      (node (ref "C72") (pin "2") (pinfunction "2_2") (pintype "unspecified"))
      (node (ref "C74") (pin "2") (pinfunction "2_2") (pintype "unspecified"))
      (node (ref "C75") (pin "2") (pinfunction "2_2") (pintype "unspecified"))
      (node (ref "C76") (pin "2") (pinfunction "2_2") (pintype "unspecified"))
      (node (ref "C77") (pin "2") (pinfunction "2_2") (pintype "unspecified"))
      (node (ref "C78") (pin "2") (pinfunction "2_2") (pintype "unspecified"))
      (node (ref "C86") (pin "1") (pinfunction "1_1") (pintype "input"))
      (node (ref "R52") (pin "1") (pinfunction "1_1") (pintype "input"))
      (node (ref "R53") (pin "2") (pinfunction "2_2") (pintype "input"))
      (node (ref "STICK-L") (pin "3") (pinfunction "3_3") (pintype "unspecified"))
      (node (ref "STICK-R") (pin "3") (pinfunction "3_3") (pintype "unspecified"))
      (node (ref "U16") (pin "1") (pinfunction "IOVDD_1") (pintype "bidirectional"))
      (node (ref "U16") (pin "10") (pinfunction "IOVDD_10") (pintype "bidirectional"))
      (node (ref "U16") (pin "22") (pinfunction "IOVDD_22") (pintype "bidirectional"))
      (node (ref "U16") (pin "33") (pinfunction "IOVDD_33") (pintype "bidirectional"))
      (node (ref "U16") (pin "42") (pinfunction "IOVDD_42") (pintype "bidirectional"))
      (node (ref "U16") (pin "43") (pinfunction "ADC_AVDD_43") (pintype "bidirectional"))
      (node (ref "U16") (pin "44") (pinfunction "VREG_IN_44") (pintype "bidirectional"))
      (node (ref "U16") (pin "48") (pinfunction "USB_VDD_48") (pintype "bidirectional"))
      (node (ref "U16") (pin "49") (pinfunction "IOVDD_49") (pintype "bidirectional"))
      (node (ref "U17") (pin "8") (pinfunction "VCC_8") (pintype "unspecified"))
      (node (ref "U18") (pin "5") (pinfunction "VOUT_5") (pintype "unspecified"))
      (node (ref "U20") (pin "1") (pinfunction "CPVDD_1") (pintype "input"))
      (node (ref "U20") (pin "17") (pinfunction "XSMT_17") (pintype "input"))
      (node (ref "U20") (pin "20") (pinfunction "DVDD_20") (pintype "input"))
      (node (ref "U20") (pin "8") (pinfunction "AVDD_8") (pintype "input"))
      (node (ref "U21") (pin "13") (pinfunction "EN_13") (pintype "unspecified"))
      (node (ref "U21") (pin "14") (pinfunction "PVDD_14") (pintype "unspecified"))
      (node (ref "U21") (pin "6") (pinfunction "G0_6") (pintype "unspecified"))
    )
    (net (code "3") (name "/+5V") (class "Default")
      (node (ref "C25") (pin "1") (pinfunction "1_1") (pintype "unspecified"))
      (node (ref "C3") (pin "1") (pinfunction "1_1") (pintype "unspecified"))
      (node (ref "C96") (pin "2") (pinfunction "2_2") (pintype "input"))
      (node (ref "C97") (pin "2") (pinfunction "2_2") (pintype "unspecified"))
      (node (ref "C98") (pin "2") (pinfunction "2_2") (pintype "input"))
      (node (ref "C99") (pin "2") (pinfunction "2_2") (pintype "unspecified"))
      (node (ref "FPC4") (pin "18") (pinfunction "18_18") (pintype "input"))
      (node (ref "FPC4") (pin "19") (pinfunction "19_19") (pintype "input"))
      (node (ref "FPC4") (pin "20") (pinfunction "20_20") (pintype "input"))
      (node (ref "FPC4") (pin "21") (pinfunction "21_21") (pintype "input"))
      (node (ref "R55") (pin "1") (pinfunction "1_1") (pintype "input"))
      (node (ref "R58") (pin "1") (pinfunction "1_1") (pintype "input"))
      (node (ref "U1") (pin "1") (pinfunction "IN_1") (pintype "unspecified"))
      (node (ref "U1") (pin "3") (pinfunction "EN/EN#_3") (pintype "unspecified"))
      (node (ref "U18") (pin "1") (pinfunction "VIN_1") (pintype "unspecified"))
      (node (ref "U22") (pin "6") (pinfunction "VCC_6") (pintype "unspecified"))
      (node (ref "U23") (pin "6") (pinfunction "VCC_6") (pintype "unspecified"))
    )
    (net (code "4") (name "/AMP_SW") (class "Default")
      (node (ref "CN13") (pin "2") (pinfunction "2_2") (pintype "unspecified"))
      (node (ref "R58") (pin "2") (pinfunction "2_2") (pintype "input"))
      (node (ref "U22") (pin "1") (pinfunction "CTRL_1") (pintype "unspecified"))
      (node (ref "U23") (pin "1") (pinfunction "CTRL_1") (pintype "unspecified"))
    )
    (net (code "5") (name "/BCK") (class "Default")
      (node (ref "FPC4") (pin "16") (pinfunction "16_16") (pintype "input"))
      (node (ref "U20") (pin "13") (pinfunction "BCK_13") (pintype "input"))
    )
    (net (code "6") (name "/DACL") (class "Default")
      (node (ref "C91") (pin "1") (pinfunction "1_1") (pintype "input"))
      (node (ref "R56") (pin "1") (pinfunction "1_1") (pintype "input"))
      (node (ref "U20") (pin "6") (pinfunction "OUTL_6") (pintype "input"))
    )
    (net (code "7") (name "/DACR") (class "Default")
      (node (ref "C94") (pin "1") (pinfunction "1_1") (pintype "input"))
      (node (ref "R57") (pin "1") (pinfunction "1_1") (pintype "input"))
      (node (ref "U20") (pin "7") (pinfunction "OUTR_7") (pintype "input"))
    )
    (net (code "8") (name "/DIN") (class "Default")
      (node (ref "FPC4") (pin "14") (pinfunction "14_14") (pintype "input"))
      (node (ref "U20") (pin "14") (pinfunction "DIN_14") (pintype "input"))
    )
    (net (code "9") (name "/GPIO4") (class "Default")
      (node (ref "FPC4") (pin "12") (pinfunction "12_12") (pintype "input"))
    )
    (net (code "10") (name "/GPIO5") (class "Default")
      (node (ref "FPC4") (pin "11") (pinfunction "11_11") (pintype "input"))
    )
    (net (code "11") (name "/GPIO6") (class "Default")
      (node (ref "FPC4") (pin "10") (pinfunction "10_10") (pintype "input"))
    )
    (net (code "12") (name "/GPIO7") (class "Default")
      (node (ref "FPC4") (pin "9") (pinfunction "9_9") (pintype "input"))
    )
    (net (code "13") (name "/GPIO8") (class "Default")
      (node (ref "FPC4") (pin "8") (pinfunction "8_8") (pintype "input"))
    )
    (net (code "14") (name "/L+") (class "Default")
      (node (ref "SPKR_L") (pin "1") (pinfunction "1_1") (pintype "unspecified"))
      (node (ref "U22") (pin "8") (pinfunction "VoP_8") (pintype "unspecified"))
    )
    (net (code "15") (name "/L-") (class "Default")
      (node (ref "SPKR_L") (pin "2") (pinfunction "2_2") (pintype "unspecified"))
      (node (ref "U22") (pin "5") (pinfunction "VON_5") (pintype "unspecified"))
    )
    (net (code "16") (name "/LRCK") (class "Default")
      (node (ref "FPC4") (pin "15") (pinfunction "15_15") (pintype "input"))
      (node (ref "U20") (pin "15") (pinfunction "LRCK_15") (pintype "input"))
    )
    (net (code "17") (name "/PWR_BUTTON") (class "Default")
      (node (ref "FPC4") (pin "7") (pinfunction "7_7") (pintype "input"))
      (node (ref "PWR") (pin "1") (pinfunction "1_1") (pintype "unspecified"))
    )
    (net (code "18") (name "/R+") (class "Default")
      (node (ref "SPKR_R") (pin "1") (pinfunction "1_1") (pintype "unspecified"))
      (node (ref "U23") (pin "8") (pinfunction "VoP_8") (pintype "unspecified"))
    )
    (net (code "19") (name "/R-") (class "Default")
      (node (ref "SPKR_R") (pin "2") (pinfunction "2_2") (pintype "unspecified"))
      (node (ref "U23") (pin "5") (pinfunction "VON_5") (pintype "unspecified"))
    )
    (net (code "20") (name "/USB3-0-D_N") (class "Default")
      (node (ref "FPC4") (pin "3") (pinfunction "3_3") (pintype "input"))
      (node (ref "USBC2") (pin "A7") (pinfunction "DN1_A7") (pintype "unspecified"))
      (node (ref "USBC2") (pin "B7") (pinfunction "DN2_B7") (pintype "unspecified"))
    )
    (net (code "21") (name "/USB3-0-D_P") (class "Default")
      (node (ref "FPC4") (pin "2") (pinfunction "2_2") (pintype "input"))
      (node (ref "USBC2") (pin "A6") (pinfunction "DP1_A6") (pintype "unspecified"))
      (node (ref "USBC2") (pin "B6") (pinfunction "DP2_B6") (pintype "unspecified"))
    )
    (net (code "22") (name "/VBUS") (class "Default")
      (node (ref "C38") (pin "1") (pinfunction "1_1") (pintype "unspecified"))
      (node (ref "C39") (pin "1") (pinfunction "1_1") (pintype "unspecified"))
      (node (ref "C5") (pin "1") (pinfunction "1_1") (pintype "unspecified"))
      (node (ref "C6") (pin "1") (pinfunction "1_1") (pintype "unspecified"))
      (node (ref "R43") (pin "2") (pinfunction "2_2") (pintype "input"))
      (node (ref "R44") (pin "2") (pinfunction "2_2") (pintype "input"))
      (node (ref "U1") (pin "6") (pinfunction "OUT_6") (pintype "unspecified"))
      (node (ref "USBC2") (pin "A4") (pinfunction "VBUS_A4") (pintype "unspecified"))
      (node (ref "USBC2") (pin "A9") (pinfunction "VBUS_A9") (pintype "unspecified"))
      (node (ref "USBC2") (pin "B4") (pinfunction "VBUS_B4") (pintype "unspecified"))
      (node (ref "USBC2") (pin "B9") (pinfunction "VBUS_B9") (pintype "unspecified"))
    )
    (net (code "23") (name "/XIN") (class "Default")
      (node (ref "C2") (pin "2") (pinfunction "2_2") (pintype "input"))
      (node (ref "U16") (pin "20") (pinfunction "XIN_20") (pintype "input"))
      (node (ref "X1") (pin "1") (pinfunction "OSC1_1") (pintype "unspecified"))
    )
    (net (code "24") (name "/XOUT") (class "Default")
      (node (ref "R49") (pin "2") (pinfunction "2_2") (pintype "input"))
      (node (ref "U16") (pin "21") (pinfunction "XOUT_21") (pintype "unspecified"))
    )
    (net (code "25") (name "A1") (class "Default")
      (node (ref "A1") (pin "1") (pinfunction "1_1") (pintype "unspecified"))
      (node (ref "U16") (pin "17") (pinfunction "GPIO14_17") (pintype "bidirectional"))
    )
    (net (code "26") (name "A2") (class "Default")
      (node (ref "A2") (pin "1") (pinfunction "1_1") (pintype "unspecified"))
      (node (ref "U16") (pin "31") (pinfunction "GPIO20_31") (pintype "bidirectional"))
    )
    (net (code "27") (name "DOWN") (class "Default")
      (node (ref "DPAD_DOWN") (pin "1") (pinfunction "1_1") (pintype "unspecified"))
      (node (ref "U16") (pin "29") (pinfunction "GPIO18_29") (pintype "bidirectional"))
    )
    (net (code "28") (name "GND") (class "Default")
      (node (ref "A") (pin "3") (pinfunction "3_3") (pintype "unspecified"))
      (node (ref "A") (pin "4") (pinfunction "4_4") (pintype "unspecified"))
      (node (ref "A1") (pin "2") (pinfunction "2_2") (pintype "unspecified"))
      (node (ref "A2") (pin "2") (pinfunction "2_2") (pintype "unspecified"))
      (node (ref "B") (pin "3") (pinfunction "3_3") (pintype "unspecified"))
      (node (ref "B") (pin "4") (pinfunction "4_4") (pintype "unspecified"))
      (node (ref "BACK") (pin "3") (pinfunction "3_3") (pintype "unspecified"))
      (node (ref "BACK") (pin "4") (pinfunction "4_4") (pintype "unspecified"))
      (node (ref "BOOT1") (pin "2") (pinfunction "2_2") (pintype "unspecified"))
      (node (ref "C13") (pin "1") (pinfunction "1_1") (pintype "input"))
      (node (ref "C14") (pin "1") (pinfunction "1_1") (pintype "input"))
      (node (ref "C15") (pin "1") (pinfunction "1_1") (pintype "input"))
      (node (ref "C16") (pin "1") (pinfunction "1_1") (pintype "input"))
      (node (ref "C2") (pin "1") (pinfunction "1_1") (pintype "input"))
      (node (ref "C25") (pin "2") (pinfunction "2_2") (pintype "unspecified"))
      (node (ref "C3") (pin "2") (pinfunction "2_2") (pintype "unspecified"))
      (node (ref "C33") (pin "2") (pinfunction "2_2") (pintype "unspecified"))
      (node (ref "C38") (pin "2") (pinfunction "2_2") (pintype "unspecified"))
      (node (ref "C39") (pin "2") (pinfunction "2_2") (pintype "unspecified"))
      (node (ref "C5") (pin "2") (pinfunction "2_2") (pintype "unspecified"))
      (node (ref "C55") (pin "1") (pinfunction "1_1") (pintype "input"))
      (node (ref "C56") (pin "2") (pinfunction "2_2") (pintype "unspecified"))
      (node (ref "C57") (pin "2") (pinfunction "2_2") (pintype "unspecified"))
      (node (ref "C58") (pin "1") (pinfunction "1_1") (pintype "input"))
      (node (ref "C59") (pin "1") (pinfunction "1_1") (pintype "input"))
      (node (ref "C6") (pin "2") (pinfunction "2_2") (pintype "unspecified"))
      (node (ref "C60") (pin "1") (pinfunction "1_1") (pintype "input"))
      (node (ref "C61") (pin "1") (pinfunction "1_1") (pintype "input"))
      (node (ref "C62") (pin "1") (pinfunction "1_1") (pintype "input"))
      (node (ref "C63") (pin "1") (pinfunction "1_1") (pintype "input"))
      (node (ref "C64") (pin "2") (pinfunction "2_2") (pintype "input"))
      (node (ref "C65") (pin "2") (pinfunction "2_2") (pintype "input"))
      (node (ref "C7") (pin "1") (pinfunction "1_1") (pintype "input"))
      (node (ref "C71") (pin "1") (pinfunction "1_1") (pintype "input"))
      (node (ref "C72") (pin "1") (pinfunction "1_1") (pintype "unspecified"))
      (node (ref "C73") (pin "2") (pinfunction "2_2") (pintype "unspecified"))
      (node (ref "C74") (pin "1") (pinfunction "1_1") (pintype "unspecified"))
      (node (ref "C75") (pin "1") (pinfunction "1_1") (pintype "unspecified"))
      (node (ref "C76") (pin "1") (pinfunction "1_1") (pintype "unspecified"))
      (node (ref "C77") (pin "1") (pinfunction "1_1") (pintype "unspecified"))
      (node (ref "C78") (pin "1") (pinfunction "1_1") (pintype "unspecified"))
      (node (ref "C79") (pin "2") (pinfunction "2_2") (pintype "unspecified"))
      (node (ref "C80") (pin "2") (pinfunction "2_2") (pintype "input"))
      (node (ref "C81") (pin "2") (pinfunction "2_2") (pintype "input"))
      (node (ref "C84") (pin "2") (pinfunction "2_2") (pintype "unspecified"))
      (node (ref "C85") (pin "2") (pinfunction "2_2") (pintype "unspecified"))
      (node (ref "C86") (pin "2") (pinfunction "2_2") (pintype "input"))
      (node (ref "C87") (pin "2") (pinfunction "2_2") (pintype "unspecified"))
      (node (ref "C89") (pin "1") (pinfunction "1_1") (pintype "unspecified"))
      (node (ref "C90") (pin "2") (pinfunction "2_2") (pintype "unspecified"))
      (node (ref "C92") (pin "1") (pinfunction "1_1") (pintype "input"))
      (node (ref "C93") (pin "2") (pinfunction "2_2") (pintype "unspecified"))
      (node (ref "C95") (pin "1") (pinfunction "1_1") (pintype "input"))
      (node (ref "C96") (pin "1") (pinfunction "1_1") (pintype "input"))
      (node (ref "C97") (pin "1") (pinfunction "1_1") (pintype "unspecified"))
      (node (ref "C98") (pin "1") (pinfunction "1_1") (pintype "input"))
      (node (ref "C99") (pin "1") (pinfunction "1_1") (pintype "unspecified"))
      (node (ref "CN13") (pin "1") (pinfunction "1_1") (pintype "unspecified"))
      (node (ref "DPAD_DOWN") (pin "3") (pinfunction "3_3") (pintype "unspecified"))
      (node (ref "DPAD_DOWN") (pin "4") (pinfunction "4_4") (pintype "unspecified"))
      (node (ref "DPAD_LEFT") (pin "3") (pinfunction "3_3") (pintype "unspecified"))
      (node (ref "DPAD_LEFT") (pin "4") (pinfunction "4_4") (pintype "unspecified"))
      (node (ref "DPAD_RIGHT") (pin "3") (pinfunction "3_3") (pintype "unspecified"))
      (node (ref "DPAD_RIGHT") (pin "4") (pinfunction "4_4") (pintype "unspecified"))
      (node (ref "DPAD_UP") (pin "3") (pinfunction "3_3") (pintype "unspecified"))
      (node (ref "DPAD_UP") (pin "4") (pinfunction "4_4") (pintype "unspecified"))
      (node (ref "FPC4") (pin "1") (pinfunction "1_1") (pintype "input"))
      (node (ref "FPC4") (pin "13") (pinfunction "13_13") (pintype "input"))
      (node (ref "FPC4") (pin "17") (pinfunction "17_17") (pintype "input"))
      (node (ref "FPC4") (pin "22") (pinfunction "22_22") (pintype "input"))
      (node (ref "FPC4") (pin "6") (pinfunction "6_6") (pintype "input"))
      (node (ref "LB") (pin "2") (pinfunction "2_2") (pintype "unspecified"))
      (node (ref "LS") (pin "3") (pinfunction "3_3") (pintype "unspecified"))
      (node (ref "LS") (pin "4") (pinfunction "4_4") (pintype "unspecified"))
      (node (ref "LT") (pin "2") (pinfunction "2_2") (pintype "unspecified"))
      (node (ref "PWR") (pin "2") (pinfunction "2_2") (pintype "unspecified"))
      (node (ref "R2") (pin "2") (pinfunction "2_2") (pintype "input"))
      (node (ref "R54") (pin "1") (pinfunction "1_1") (pintype "input"))
      (node (ref "RB") (pin "1") (pinfunction "1_1") (pintype "unspecified"))
      (node (ref "RESET1") (pin "2") (pinfunction "2_2") (pintype "unspecified"))
      (node (ref "RS") (pin "3") (pinfunction "3_3") (pintype "unspecified"))
      (node (ref "RS") (pin "4") (pinfunction "4_4") (pintype "unspecified"))
      (node (ref "RT") (pin "1") (pinfunction "1_1") (pintype "unspecified"))
      (node (ref "START") (pin "3") (pinfunction "3_3") (pintype "unspecified"))
      (node (ref "START") (pin "4") (pinfunction "4_4") (pintype "unspecified"))
      (node (ref "STICK-L") (pin "1") (pinfunction "1_1") (pintype "unspecified"))
      (node (ref "STICK-R") (pin "1") (pinfunction "1_1") (pintype "unspecified"))
      (node (ref "U1") (pin "2") (pinfunction "GND_2") (pintype "unspecified"))
      (node (ref "U16") (pin "19") (pinfunction "TESTEN_19") (pintype "unspecified"))
      (node (ref "U16") (pin "57") (pinfunction "GND_57") (pintype "bidirectional"))
      (node (ref "U17") (pin "4") (pinfunction "GND_4") (pintype "unspecified"))
      (node (ref "U18") (pin "2") (pinfunction "GND_2") (pintype "unspecified"))
      (node (ref "U20") (pin "10") (pinfunction "DEMP_10") (pintype "input"))
      (node (ref "U20") (pin "11") (pinfunction "FLT_11") (pintype "input"))
      (node (ref "U20") (pin "12") (pinfunction "SCK_12") (pintype "input"))
      (node (ref "U20") (pin "16") (pinfunction "FMT_16") (pintype "input"))
      (node (ref "U20") (pin "19") (pinfunction "DGND_19") (pintype "input"))
      (node (ref "U20") (pin "3") (pinfunction "CPGND_3") (pintype "input"))
      (node (ref "U20") (pin "9") (pinfunction "AGND_9") (pintype "input"))
      (node (ref "U21") (pin "10") (pinfunction "PGND_10") (pintype "unspecified"))
      (node (ref "U21") (pin "15") (pinfunction "SGND_15") (pintype "unspecified"))
      (node (ref "U21") (pin "17") (pinfunction "EP_17") (pintype "unspecified"))
      (node (ref "U21") (pin "7") (pinfunction "G1_7") (pintype "unspecified"))
      (node (ref "U22") (pin "7") (pinfunction "GND_7") (pintype "unspecified"))
      (node (ref "U23") (pin "7") (pinfunction "GND_7") (pintype "unspecified"))
      (node (ref "USBC2") (pin "0") (pinfunction "SH_0") (pintype "unspecified"))
      (node (ref "USBC2") (pin "1") (pinfunction "SH_1") (pintype "unspecified"))
      (node (ref "USBC2") (pin "2") (pinfunction "SH_2") (pintype "unspecified"))
      (node (ref "USBC2") (pin "3") (pinfunction "SH_3") (pintype "unspecified"))
      (node (ref "USBC2") (pin "A1") (pinfunction "GND_A1") (pintype "unspecified"))
      (node (ref "USBC2") (pin "A12") (pinfunction "GND_A12") (pintype "unspecified"))
      (node (ref "USBC2") (pin "B1") (pinfunction "GND_B1") (pintype "unspecified"))
      (node (ref "USBC2") (pin "B12") (pinfunction "GND_B12") (pintype "unspecified"))
      (node (ref "X") (pin "3") (pinfunction "3_3") (pintype "unspecified"))
      (node (ref "X") (pin "4") (pinfunction "4_4") (pintype "unspecified"))
      (node (ref "Y") (pin "3") (pinfunction "3_3") (pintype "unspecified"))
      (node (ref "Y") (pin "4") (pinfunction "4_4") (pintype "unspecified"))
    )
    (net (code "29") (name "J1-X") (class "Default")
      (node (ref "STICK-L") (pin "4") (pinfunction "4_4") (pintype "unspecified"))
      (node (ref "U16") (pin "38") (pinfunction "GPIO26_ADC0_38") (pintype "bidirectional"))
    )
    (net (code "30") (name "J1-Y") (class "Default")
      (node (ref "STICK-L") (pin "2") (pinfunction "2_2") (pintype "unspecified"))
      (node (ref "U16") (pin "39") (pinfunction "GPIO27_ADC1_39") (pintype "bidirectional"))
    )
    (net (code "31") (name "J2-X") (class "Default")
      (node (ref "STICK-R") (pin "4") (pinfunction "4_4") (pintype "unspecified"))
      (node (ref "U16") (pin "40") (pinfunction "GPIO28_ADC2_40") (pintype "bidirectional"))
    )
    (net (code "32") (name "J2-Y") (class "Default")
      (node (ref "STICK-R") (pin "2") (pinfunction "2_2") (pintype "unspecified"))
      (node (ref "U16") (pin "41") (pinfunction "GPIO29_ADC3_41") (pintype "bidirectional"))
    )
    (net (code "33") (name "K1") (class "Default")
      (node (ref "A") (pin "2") (pinfunction "2_2") (pintype "unspecified"))
      (node (ref "U16") (pin "11") (pinfunction "GPIO8_11") (pintype "bidirectional"))
    )
    (net (code "34") (name "K2") (class "Default")
      (node (ref "B") (pin "2") (pinfunction "2_2") (pintype "unspecified"))
      (node (ref "U16") (pin "9") (pinfunction "GPIO7_9") (pintype "bidirectional"))
    )
    (net (code "35") (name "K3") (class "Default")
      (node (ref "RT") (pin "2") (pinfunction "2_2") (pintype "unspecified"))
      (node (ref "U16") (pin "8") (pinfunction "GPIO6_8") (pintype "bidirectional"))
    )
    (net (code "36") (name "K4") (class "Default")
      (node (ref "LT") (pin "1") (pinfunction "1_1") (pintype "unspecified"))
      (node (ref "U16") (pin "7") (pinfunction "GPIO5_7") (pintype "bidirectional"))
    )
    (net (code "37") (name "L3") (class "Default")
      (node (ref "LS") (pin "2") (pinfunction "2_2") (pintype "unspecified"))
      (node (ref "U16") (pin "32") (pinfunction "GPIO21_32") (pintype "bidirectional"))
    )
    (net (code "38") (name "LEFT") (class "Default")
      (node (ref "DPAD_LEFT") (pin "1") (pinfunction "1_1") (pintype "unspecified"))
      (node (ref "U16") (pin "27") (pinfunction "GPIO16_27") (pintype "bidirectional"))
    )
    (net (code "39") (name "Net-(BOOT1-Pad1)") (class "Default")
      (node (ref "BOOT1") (pin "1") (pinfunction "1_1") (pintype "unspecified"))
      (node (ref "R51") (pin "1") (pinfunction "1_1") (pintype "input"))
    )
    (net (code "40") (name "Net-(C63-Pad2)") (class "Default")
      (node (ref "C63") (pin "2") (pinfunction "2_2") (pintype "input"))
      (node (ref "R50") (pin "1") (pinfunction "1_1") (pintype "input"))
      (node (ref "RESET1") (pin "1") (pinfunction "1_1") (pintype "unspecified"))
    )
    (net (code "41") (name "Net-(C80-Pad1)") (class "Default")
      (node (ref "C80") (pin "1") (pinfunction "1_1") (pintype "input"))
      (node (ref "C82") (pin "2") (pinfunction "2_2") (pintype "unspecified"))
      (node (ref "R56") (pin "2") (pinfunction "2_2") (pintype "input"))
    )
    (net (code "42") (name "Net-(C81-Pad1)") (class "Default")
      (node (ref "C81") (pin "1") (pinfunction "1_1") (pintype "input"))
      (node (ref "C83") (pin "2") (pinfunction "2_2") (pintype "unspecified"))
      (node (ref "R57") (pin "2") (pinfunction "2_2") (pintype "input"))
    )
    (net (code "43") (name "Net-(C91-Pad2)") (class "Default")
      (node (ref "C91") (pin "2") (pinfunction "2_2") (pintype "input"))
      (node (ref "R63") (pin "1") (pinfunction "1_1") (pintype "input"))
    )
    (net (code "44") (name "Net-(C92-Pad2)") (class "Default")
      (node (ref "C92") (pin "2") (pinfunction "2_2") (pintype "input"))
      (node (ref "R64") (pin "1") (pinfunction "1_1") (pintype "input"))
    )
    (net (code "45") (name "Net-(C94-Pad2)") (class "Default")
      (node (ref "C94") (pin "2") (pinfunction "2_2") (pintype "input"))
      (node (ref "R61") (pin "1") (pinfunction "1_1") (pintype "input"))
    )
    (net (code "46") (name "Net-(C95-Pad2)") (class "Default")
      (node (ref "C95") (pin "2") (pinfunction "2_2") (pintype "input"))
      (node (ref "R62") (pin "1") (pinfunction "1_1") (pintype "input"))
    )
    (net (code "47") (name "Net-(LED3-A)") (class "Default")
      (node (ref "LED3") (pin "2") (pinfunction "A_2") (pintype "unspecified"))
      (node (ref "U16") (pin "37") (pinfunction "GPIO25_37") (pintype "bidirectional"))
    )
    (net (code "48") (name "Net-(LED3-K)") (class "Default")
      (node (ref "LED3") (pin "1") (pinfunction "K_1") (pintype "unspecified"))
      (node (ref "R54") (pin "2") (pinfunction "2_2") (pintype "input"))
    )
    (net (code "49") (name "Net-(U1-ILIM)") (class "Default")
      (node (ref "R2") (pin "1") (pinfunction "1_1") (pintype "input"))
      (node (ref "U1") (pin "5") (pinfunction "ILIM_5") (pintype "unspecified"))
    )
    (net (code "50") (name "Net-(U16-RUN)") (class "Default")
      (node (ref "R50") (pin "2") (pinfunction "2_2") (pintype "input"))
      (node (ref "R52") (pin "2") (pinfunction "2_2") (pintype "input"))
      (node (ref "U16") (pin "26") (pinfunction "RUN_26") (pintype "input"))
    )
    (net (code "51") (name "Net-(U16-USB_DM)") (class "Default")
      (node (ref "R48") (pin "1") (pinfunction "1_1") (pintype "input"))
      (node (ref "U16") (pin "46") (pinfunction "USB_DM_46") (pintype "bidirectional"))
    )
    (net (code "52") (name "Net-(U16-USB_DP)") (class "Default")
      (node (ref "R47") (pin "2") (pinfunction "2_2") (pintype "input"))
      (node (ref "U16") (pin "47") (pinfunction "USB_DP_47") (pintype "bidirectional"))
    )
    (net (code "53") (name "Net-(U18-EN)") (class "Default")
      (node (ref "R55") (pin "2") (pinfunction "2_2") (pintype "input"))
      (node (ref "U18") (pin "3") (pinfunction "EN_3") (pintype "unspecified"))
    )
    (net (code "54") (name "Net-(U20-CAPM)") (class "Default")
      (node (ref "C70") (pin "2") (pinfunction "2_2") (pintype "input"))
      (node (ref "U20") (pin "4") (pinfunction "CAPM_4") (pintype "input"))
    )
    (net (code "55") (name "Net-(U20-CAPP)") (class "Default")
      (node (ref "C70") (pin "1") (pinfunction "1_1") (pintype "input"))
      (node (ref "U20") (pin "2") (pinfunction "CAPP_2") (pintype "input"))
    )
    (net (code "56") (name "Net-(U20-LDOO)") (class "Default")
      (node (ref "C73") (pin "1") (pinfunction "1_1") (pintype "unspecified"))
      (node (ref "C79") (pin "1") (pinfunction "1_1") (pintype "unspecified"))
      (node (ref "U20") (pin "18") (pinfunction "LDOO_18") (pintype "input"))
    )
    (net (code "57") (name "Net-(U20-VNEG)") (class "Default")
      (node (ref "C71") (pin "2") (pinfunction "2_2") (pintype "input"))
      (node (ref "U20") (pin "5") (pinfunction "VNEG_5") (pintype "input"))
    )
    (net (code "58") (name "Net-(U21-CAP+)") (class "Default")
      (node (ref "C88") (pin "2") (pinfunction "2_2") (pintype "unspecified"))
      (node (ref "U21") (pin "11") (pinfunction "CAP+_11") (pintype "unspecified"))
    )
    (net (code "59") (name "Net-(U21-CAP-)") (class "Default")
      (node (ref "C88") (pin "1") (pinfunction "1_1") (pintype "unspecified"))
      (node (ref "U21") (pin "9") (pinfunction "CAP-_9") (pintype "unspecified"))
    )
    (net (code "60") (name "Net-(U21-HPVDD)") (class "Default")
      (node (ref "C87") (pin "1") (pinfunction "1_1") (pintype "unspecified"))
      (node (ref "U21") (pin "12") (pinfunction "HPVDD_12") (pintype "unspecified"))
    )
    (net (code "61") (name "Net-(U21-HPVSS)") (class "Default")
      (node (ref "C89") (pin "2") (pinfunction "2_2") (pintype "unspecified"))
      (node (ref "U21") (pin "8") (pinfunction "HPVSS_8") (pintype "unspecified"))
    )
    (net (code "62") (name "Net-(U21-INL+)") (class "Default")
      (node (ref "C82") (pin "1") (pinfunction "1_1") (pintype "unspecified"))
      (node (ref "U21") (pin "2") (pinfunction "INL+_2") (pintype "unspecified"))
    )
    (net (code "63") (name "Net-(U21-INL-)") (class "Default")
      (node (ref "C84") (pin "1") (pinfunction "1_1") (pintype "unspecified"))
      (node (ref "U21") (pin "1") (pinfunction "INL-_1") (pintype "unspecified"))
    )
    (net (code "64") (name "Net-(U21-INR+)") (class "Default")
      (node (ref "C83") (pin "1") (pinfunction "1_1") (pintype "unspecified"))
      (node (ref "U21") (pin "3") (pinfunction "INR+_3") (pintype "unspecified"))
    )
    (net (code "65") (name "Net-(U21-INR-)") (class "Default")
      (node (ref "C85") (pin "1") (pinfunction "1_1") (pintype "unspecified"))
      (node (ref "U21") (pin "4") (pinfunction "INR-_4") (pintype "unspecified"))
    )
    (net (code "66") (name "Net-(U21-OUTL)") (class "Default")
      (node (ref "CN13") (pin "4") (pinfunction "4_4") (pintype "unspecified"))
      (node (ref "CN13") (pin "5") (pinfunction "5_5") (pintype "unspecified"))
      (node (ref "U21") (pin "16") (pinfunction "OUTL_16") (pintype "unspecified"))
    )
    (net (code "67") (name "Net-(U21-OUTR)") (class "Default")
      (node (ref "CN13") (pin "3") (pinfunction "3_3") (pintype "unspecified"))
      (node (ref "U21") (pin "5") (pinfunction "OUTR_5") (pintype "unspecified"))
    )
    (net (code "68") (name "Net-(U22-Bypass)") (class "Default")
      (node (ref "C90") (pin "1") (pinfunction "1_1") (pintype "unspecified"))
      (node (ref "U22") (pin "2") (pinfunction "Bypass_2") (pintype "unspecified"))
    )
    (net (code "69") (name "Net-(U22-INN)") (class "Default")
      (node (ref "R64") (pin "2") (pinfunction "2_2") (pintype "input"))
      (node (ref "U22") (pin "4") (pinfunction "INN_4") (pintype "unspecified"))
    )
    (net (code "70") (name "Net-(U22-INP)") (class "Default")
      (node (ref "R63") (pin "2") (pinfunction "2_2") (pintype "input"))
      (node (ref "U22") (pin "3") (pinfunction "INP_3") (pintype "unspecified"))
    )
    (net (code "71") (name "Net-(U23-Bypass)") (class "Default")
      (node (ref "C93") (pin "1") (pinfunction "1_1") (pintype "unspecified"))
      (node (ref "U23") (pin "2") (pinfunction "Bypass_2") (pintype "unspecified"))
    )
    (net (code "72") (name "Net-(U23-INN)") (class "Default")
      (node (ref "R62") (pin "2") (pinfunction "2_2") (pintype "input"))
      (node (ref "U23") (pin "4") (pinfunction "INN_4") (pintype "unspecified"))
    )
    (net (code "73") (name "Net-(U23-INP)") (class "Default")
      (node (ref "R61") (pin "2") (pinfunction "2_2") (pintype "input"))
      (node (ref "U23") (pin "3") (pinfunction "INP_3") (pintype "unspecified"))
    )
    (net (code "74") (name "Net-(USBC2-CC1)") (class "Default")
      (node (ref "R44") (pin "1") (pinfunction "1_1") (pintype "input"))
      (node (ref "USBC2") (pin "A5") (pinfunction "CC1_A5") (pintype "unspecified"))
    )
    (net (code "75") (name "Net-(USBC2-CC2)") (class "Default")
      (node (ref "R43") (pin "1") (pinfunction "1_1") (pintype "input"))
      (node (ref "USBC2") (pin "B5") (pinfunction "CC2_B5") (pintype "unspecified"))
    )
    (net (code "76") (name "Net-(X1-OSC2)") (class "Default")
      (node (ref "C62") (pin "2") (pinfunction "2_2") (pintype "input"))
      (node (ref "R49") (pin "1") (pinfunction "1_1") (pintype "input"))
      (node (ref "X1") (pin "3") (pinfunction "OSC2_3") (pintype "unspecified"))
    )
    (net (code "77") (name "OPTION1") (class "Default")
      (node (ref "U16") (pin "35") (pinfunction "GPIO23_35") (pintype "bidirectional"))
    )
    (net (code "78") (name "OPTION2") (class "Default")
      (node (ref "U16") (pin "36") (pinfunction "GPIO24_36") (pintype "bidirectional"))
    )
    (net (code "79") (name "P1") (class "Default")
      (node (ref "U16") (pin "15") (pinfunction "GPIO12_15") (pintype "bidirectional"))
      (node (ref "X") (pin "1") (pinfunction "1_1") (pintype "unspecified"))
    )
    (net (code "80") (name "P2") (class "Default")
      (node (ref "U16") (pin "14") (pinfunction "GPIO11_14") (pintype "bidirectional"))
      (node (ref "Y") (pin "1") (pinfunction "1_1") (pintype "unspecified"))
    )
    (net (code "81") (name "P3") (class "Default")
      (node (ref "RB") (pin "2") (pinfunction "2_2") (pintype "unspecified"))
      (node (ref "U16") (pin "13") (pinfunction "GPIO10_13") (pintype "bidirectional"))
    )
    (net (code "82") (name "P4") (class "Default")
      (node (ref "LB") (pin "1") (pinfunction "1_1") (pintype "unspecified"))
      (node (ref "U16") (pin "12") (pinfunction "GPIO9_12") (pintype "bidirectional"))
    )
    (net (code "83") (name "QSPI_SCLK") (class "Default")
      (node (ref "U16") (pin "52") (pinfunction "QSPI_SCLK_52") (pintype "output"))
      (node (ref "U17") (pin "6") (pinfunction "CLK_6") (pintype "unspecified"))
    )
    (net (code "84") (name "QSPI_SD0") (class "Default")
      (node (ref "U16") (pin "53") (pinfunction "QSPI_SD0_53") (pintype "bidirectional"))
      (node (ref "U17") (pin "5") (pinfunction "DI_5") (pintype "unspecified"))
    )
    (net (code "85") (name "QSPI_SD1") (class "Default")
      (node (ref "U16") (pin "55") (pinfunction "QSPI_SD1_55") (pintype "bidirectional"))
      (node (ref "U17") (pin "2") (pinfunction "DO_2") (pintype "unspecified"))
    )
    (net (code "86") (name "QSPI_SD2") (class "Default")
      (node (ref "U16") (pin "54") (pinfunction "QSPI_SD2_54") (pintype "bidirectional"))
      (node (ref "U17") (pin "3") (pinfunction "IO2_3") (pintype "unspecified"))
    )
    (net (code "87") (name "QSPI_SD3") (class "Default")
      (node (ref "U16") (pin "51") (pinfunction "QSPI_SD3_51") (pintype "bidirectional"))
      (node (ref "U17") (pin "7") (pinfunction "IO3_7") (pintype "unspecified"))
    )
    (net (code "88") (name "QSPI_SS") (class "Default")
      (node (ref "R51") (pin "2") (pinfunction "2_2") (pintype "input"))
      (node (ref "R53") (pin "1") (pinfunction "1_1") (pintype "input"))
      (node (ref "U16") (pin "56") (pinfunction "QSPI_SS_56") (pintype "bidirectional"))
      (node (ref "U17") (pin "1") (pinfunction "CS#_1") (pintype "unspecified"))
    )
    (net (code "89") (name "R3") (class "Default")
      (node (ref "RS") (pin "2") (pinfunction "2_2") (pintype "unspecified"))
      (node (ref "U16") (pin "34") (pinfunction "GPIO22_34") (pintype "bidirectional"))
    )
    (net (code "90") (name "RIGHT") (class "Default")
      (node (ref "DPAD_RIGHT") (pin "2") (pinfunction "2_2") (pintype "unspecified"))
      (node (ref "U16") (pin "28") (pinfunction "GPIO17_28") (pintype "bidirectional"))
    )
    (net (code "91") (name "S1") (class "Default")
      (node (ref "BACK") (pin "2") (pinfunction "2_2") (pintype "unspecified"))
      (node (ref "U16") (pin "18") (pinfunction "GPIO15_18") (pintype "bidirectional"))
    )
    (net (code "92") (name "S2") (class "Default")
      (node (ref "START") (pin "1") (pinfunction "1_1") (pintype "unspecified"))
      (node (ref "U16") (pin "16") (pinfunction "GPIO13_16") (pintype "bidirectional"))
    )
    (net (code "93") (name "UP") (class "Default")
      (node (ref "DPAD_UP") (pin "1") (pinfunction "1_1") (pintype "unspecified"))
      (node (ref "U16") (pin "30") (pinfunction "GPIO19_30") (pintype "bidirectional"))
    )
    (net (code "94") (name "USB2_N") (class "Default")
      (node (ref "FPC4") (pin "5") (pinfunction "5_5") (pintype "input"))
      (node (ref "R48") (pin "2") (pinfunction "2_2") (pintype "input"))
    )
    (net (code "95") (name "USB2_P") (class "Default")
      (node (ref "FPC4") (pin "4") (pinfunction "4_4") (pintype "input"))
      (node (ref "R47") (pin "1") (pinfunction "1_1") (pintype "input"))
    )
    (net (code "96") (name "unconnected-(A-Pad1)") (class "Default")
      (node (ref "A") (pin "1") (pinfunction "1_1") (pintype "unspecified"))
    )
    (net (code "97") (name "unconnected-(A1-GND-Pad3)") (class "Default")
      (node (ref "A1") (pin "3") (pinfunction "GND_3") (pintype "unspecified"))
    )
    (net (code "98") (name "unconnected-(A2-GND-Pad3)") (class "Default")
      (node (ref "A2") (pin "3") (pinfunction "GND_3") (pintype "unspecified"))
    )
    (net (code "99") (name "unconnected-(B-Pad1)") (class "Default")
      (node (ref "B") (pin "1") (pinfunction "1_1") (pintype "unspecified"))
    )
    (net (code "100") (name "unconnected-(BACK-Pad1)") (class "Default")
      (node (ref "BACK") (pin "1") (pinfunction "1_1") (pintype "unspecified"))
    )
    (net (code "101") (name "unconnected-(DPAD_DOWN-Pad2)") (class "Default")
      (node (ref "DPAD_DOWN") (pin "2") (pinfunction "2_2") (pintype "unspecified"))
    )
    (net (code "102") (name "unconnected-(DPAD_LEFT-Pad2)") (class "Default")
      (node (ref "DPAD_LEFT") (pin "2") (pinfunction "2_2") (pintype "unspecified"))
    )
    (net (code "103") (name "unconnected-(DPAD_RIGHT-Pad1)") (class "Default")
      (node (ref "DPAD_RIGHT") (pin "1") (pinfunction "1_1") (pintype "unspecified"))
    )
    (net (code "104") (name "unconnected-(DPAD_UP-Pad2)") (class "Default")
      (node (ref "DPAD_UP") (pin "2") (pinfunction "2_2") (pintype "unspecified"))
    )
    (net (code "105") (name "unconnected-(FPC4-Pad23)") (class "Default")
      (node (ref "FPC4") (pin "23") (pinfunction "23_23") (pintype "input"))
    )
    (net (code "106") (name "unconnected-(FPC4-Pad24)") (class "Default")
      (node (ref "FPC4") (pin "24") (pinfunction "24_24") (pintype "input"))
    )
    (net (code "107") (name "unconnected-(LB-GND-Pad3)") (class "Default")
      (node (ref "LB") (pin "3") (pinfunction "GND_3") (pintype "unspecified"))
    )
    (net (code "108") (name "unconnected-(LS-Pad1)") (class "Default")
      (node (ref "LS") (pin "1") (pinfunction "1_1") (pintype "unspecified"))
    )
    (net (code "109") (name "unconnected-(LT-GND-Pad3)") (class "Default")
      (node (ref "LT") (pin "3") (pinfunction "GND_3") (pintype "unspecified"))
    )
    (net (code "110") (name "unconnected-(PWR-GND-Pad3)") (class "Default")
      (node (ref "PWR") (pin "3") (pinfunction "GND_3") (pintype "unspecified"))
    )
    (net (code "111") (name "unconnected-(RB-GND-Pad3)") (class "Default")
      (node (ref "RB") (pin "3") (pinfunction "GND_3") (pintype "unspecified"))
    )
    (net (code "112") (name "unconnected-(RS-Pad1)") (class "Default")
      (node (ref "RS") (pin "1") (pinfunction "1_1") (pintype "unspecified"))
    )
    (net (code "113") (name "unconnected-(RT-GND-Pad3)") (class "Default")
      (node (ref "RT") (pin "3") (pinfunction "GND_3") (pintype "unspecified"))
    )
    (net (code "114") (name "unconnected-(SPKR_L-Pad3)") (class "Default")
      (node (ref "SPKR_L") (pin "3") (pinfunction "3_3") (pintype "unspecified"))
    )
    (net (code "115") (name "unconnected-(SPKR_L-Pad4)") (class "Default")
      (node (ref "SPKR_L") (pin "4") (pinfunction "4_4") (pintype "unspecified"))
    )
    (net (code "116") (name "unconnected-(SPKR_R-Pad3)") (class "Default")
      (node (ref "SPKR_R") (pin "3") (pinfunction "3_3") (pintype "unspecified"))
    )
    (net (code "117") (name "unconnected-(SPKR_R-Pad4)") (class "Default")
      (node (ref "SPKR_R") (pin "4") (pinfunction "4_4") (pintype "unspecified"))
    )
    (net (code "118") (name "unconnected-(START-Pad2)") (class "Default")
      (node (ref "START") (pin "2") (pinfunction "2_2") (pintype "unspecified"))
    )
    (net (code "119") (name "unconnected-(STICK-L-Pad5)") (class "Default")
      (node (ref "STICK-L") (pin "5") (pinfunction "5_5") (pintype "unspecified"))
    )
    (net (code "120") (name "unconnected-(STICK-L-Pad6)") (class "Default")
      (node (ref "STICK-L") (pin "6") (pinfunction "6_6") (pintype "unspecified"))
    )
    (net (code "121") (name "unconnected-(STICK-R-Pad5)") (class "Default")
      (node (ref "STICK-R") (pin "5") (pinfunction "5_5") (pintype "unspecified"))
    )
    (net (code "122") (name "unconnected-(STICK-R-Pad6)") (class "Default")
      (node (ref "STICK-R") (pin "6") (pinfunction "6_6") (pintype "unspecified"))
    )
    (net (code "123") (name "unconnected-(U1-FAULT#-Pad4)") (class "Default")
      (node (ref "U1") (pin "4") (pinfunction "FAULT#_4") (pintype "unspecified"))
    )
    (net (code "124") (name "unconnected-(U16-GPIO0-Pad2)") (class "Default")
      (node (ref "U16") (pin "2") (pinfunction "GPIO0_2") (pintype "bidirectional+no_connect"))
    )
    (net (code "125") (name "unconnected-(U16-GPIO1-Pad3)") (class "Default")
      (node (ref "U16") (pin "3") (pinfunction "GPIO1_3") (pintype "bidirectional+no_connect"))
    )
    (net (code "126") (name "unconnected-(U16-GPIO2-Pad4)") (class "Default")
      (node (ref "U16") (pin "4") (pinfunction "GPIO2_4") (pintype "bidirectional+no_connect"))
    )
    (net (code "127") (name "unconnected-(U16-GPIO3-Pad5)") (class "Default")
      (node (ref "U16") (pin "5") (pinfunction "GPIO3_5") (pintype "bidirectional+no_connect"))
    )
    (net (code "128") (name "unconnected-(U16-GPIO4-Pad6)") (class "Default")
      (node (ref "U16") (pin "6") (pinfunction "GPIO4_6") (pintype "bidirectional+no_connect"))
    )
    (net (code "129") (name "unconnected-(U16-SWCLK-Pad24)") (class "Default")
      (node (ref "U16") (pin "24") (pinfunction "SWCLK_24") (pintype "output+no_connect"))
    )
    (net (code "130") (name "unconnected-(U16-SWD-Pad25)") (class "Default")
      (node (ref "U16") (pin "25") (pinfunction "SWD_25") (pintype "bidirectional+no_connect"))
    )
    (net (code "131") (name "unconnected-(U18-NC-Pad4)") (class "Default")
      (node (ref "U18") (pin "4") (pinfunction "NC_4") (pintype "unspecified"))
    )
    (net (code "132") (name "unconnected-(USBC2-SBU1-PadA8)") (class "Default")
      (node (ref "USBC2") (pin "A8") (pinfunction "SBU1_A8") (pintype "unspecified+no_connect"))
    )
    (net (code "133") (name "unconnected-(USBC2-SBU2-PadB8)") (class "Default")
      (node (ref "USBC2") (pin "B8") (pinfunction "SBU2_B8") (pintype "unspecified+no_connect"))
    )
    (net (code "134") (name "unconnected-(X-Pad2)") (class "Default")
      (node (ref "X") (pin "2") (pinfunction "2_2") (pintype "unspecified"))
    )
    (net (code "135") (name "unconnected-(X1-GND-Pad2)") (class "Default")
      (node (ref "X1") (pin "2") (pinfunction "GND_2") (pintype "unspecified+no_connect"))
    )
    (net (code "136") (name "unconnected-(X1-GND-Pad4)") (class "Default")
      (node (ref "X1") (pin "4") (pinfunction "GND_4") (pintype "unspecified+no_connect"))
    )
    (net (code "137") (name "unconnected-(Y-Pad2)") (class "Default")
      (node (ref "Y") (pin "2") (pinfunction "2_2") (pintype "unspecified"))
    )
  )
)
